# Mounting_Holes.net
KiCad netlist of a schematic drawn in Altium Designer
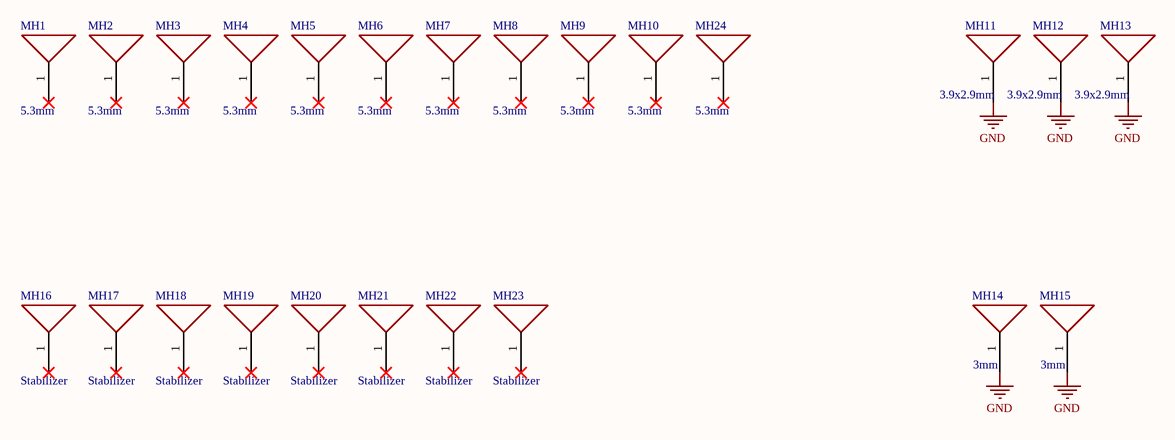
[diagram p0: Mounting_Holes.SchDoc]

(export (version "E")
  (design (tool "Eeschema 10.0.6"))
  (components
    (comp (ref "MH1")
      (value "5.3mm")
      (footprint "MTH_ROUND_5.35D")
      (libsource (lib "KeyBored_PCB_ThomasLajoie_2025") (part "Mounting Hole"))
    )
    (comp (ref "MH2")
      (value "5.3mm")
      (footprint "MTH_ROUND_5.35D")
      (libsource (lib "KeyBored_PCB_ThomasLajoie_2025") (part "Mounting Hole"))
    )
    (comp (ref "MH3")
      (value "5.3mm")
      (footprint "MTH_ROUND_5.35D")
      (libsource (lib "KeyBored_PCB_ThomasLajoie_2025") (part "Mounting Hole"))
    )
    (comp (ref "MH4")
      (value "5.3mm")
      (footprint "MTH_ROUND_5.35D")
      (libsource (lib "KeyBored_PCB_ThomasLajoie_2025") (part "Mounting Hole"))
    )
    (comp (ref "MH5")
      (value "5.3mm")
      (footprint "MTH_ROUND_5.35D")
      (libsource (lib "KeyBored_PCB_ThomasLajoie_2025") (part "Mounting Hole"))
    )
    (comp (ref "MH6")
      (value "5.3mm")
      (footprint "MTH_ROUND_5.35D")
      (libsource (lib "KeyBored_PCB_ThomasLajoie_2025") (part "Mounting Hole"))
    )
    (comp (ref "MH7")
      (value "5.3mm")
      (footprint "MTH_ROUND_5.35D")
      (libsource (lib "KeyBored_PCB_ThomasLajoie_2025") (part "Mounting Hole"))
    )
    (comp (ref "MH8")
      (value "5.3mm")
      (footprint "MTH_ROUND_5.35D")
      (libsource (lib "KeyBored_PCB_ThomasLajoie_2025") (part "Mounting Hole"))
    )
    (comp (ref "MH9")
      (value "5.3mm")
      (footprint "MTH_ROUND_5.35D")
      (libsource (lib "KeyBored_PCB_ThomasLajoie_2025") (part "Mounting Hole"))
    )
    (comp (ref "MH10")
      (value "5.3mm")
      (footprint "MTH_ROUND_5.35D")
      (libsource (lib "KeyBored_PCB_ThomasLajoie_2025") (part "Mounting Hole"))
    )
    (comp (ref "MH11")
      (value "3.9x2.9mm")
      (footprint "MTH_OBLONG_3.9x2.9_PL")
      (libsource (lib "KeyBored_PCB_ThomasLajoie_2025") (part "Mounting Hole"))
    )
    (comp (ref "MH12")
      (value "3.9x2.9mm")
      (footprint "MTH_OBLONG_3.9x2.9_PL")
      (libsource (lib "KeyBored_PCB_ThomasLajoie_2025") (part "Mounting Hole"))
    )
    (comp (ref "MH13")
      (value "3.9x2.9mm")
      (footprint "MTH_OBLONG_3.9x2.9_PL")
      (libsource (lib "KeyBored_PCB_ThomasLajoie_2025") (part "Mounting Hole"))
    )
    (comp (ref "MH14")
      (value "3mm")
      (footprint "MTH_ROUND_3D_PL")
      (libsource (lib "KeyBored_PCB_ThomasLajoie_2025") (part "Mounting Hole"))
    )
    (comp (ref "MH15")
      (value "3mm")
      (footprint "MTH_ROUND_3D_PL")
      (libsource (lib "KeyBored_PCB_ThomasLajoie_2025") (part "Mounting Hole"))
    )
    (comp (ref "MH16")
      (value "Stabilizer")
      (footprint "STABILIZERS_HOLE")
      (libsource (lib "KeyBored_PCB_ThomasLajoie_2025") (part "Mounting Hole"))
    )
    (comp (ref "MH17")
      (value "Stabilizer")
      (footprint "STABILIZERS_HOLE")
      (libsource (lib "KeyBored_PCB_ThomasLajoie_2025") (part "Mounting Hole"))
    )
    (comp (ref "MH18")
      (value "Stabilizer")
      (footprint "STABILIZERS_HOLE")
      (libsource (lib "KeyBored_PCB_ThomasLajoie_2025") (part "Mounting Hole"))
    )
    (comp (ref "MH19")
      (value "Stabilizer")
      (footprint "STABILIZERS_HOLE")
      (libsource (lib "KeyBored_PCB_ThomasLajoie_2025") (part "Mounting Hole"))
    )
    (comp (ref "MH20")
      (value "Stabilizer")
      (footprint "STABILIZERS_HOLE")
      (libsource (lib "KeyBored_PCB_ThomasLajoie_2025") (part "Mounting Hole"))
    )
    (comp (ref "MH21")
      (value "Stabilizer")
      (footprint "STABILIZERS_HOLE")
      (libsource (lib "KeyBored_PCB_ThomasLajoie_2025") (part "Mounting Hole"))
    )
    (comp (ref "MH22")
      (value "Stabilizer")
      (footprint "STABILIZERS_HOLE")
      (libsource (lib "KeyBored_PCB_ThomasLajoie_2025") (part "Mounting Hole"))
    )
    (comp (ref "MH23")
      (value "Stabilizer")
      (footprint "STABILIZERS_HOLE")
      (libsource (lib "KeyBored_PCB_ThomasLajoie_2025") (part "Mounting Hole"))
    )
    (comp (ref "MH24")
      (value "5.3mm")
      (footprint "MTH_ROUND_5.35D")
      (libsource (lib "KeyBored_PCB_ThomasLajoie_2025") (part "Mounting Hole"))
    )
  )
  (nets
    (net (code "1") (name "GND") (class "Default")
      (node (ref "MH11") (pin "1") (pintype "power_in"))
      (node (ref "MH12") (pin "1") (pintype "power_in"))
      (node (ref "MH13") (pin "1") (pintype "power_in"))
      (node (ref "MH14") (pin "1") (pintype "power_in"))
      (node (ref "MH15") (pin "1") (pintype "power_in"))
    )
    (net (code "2") (name "unconnected-(MH1-Pad1)") (class "Default")
      (node (ref "MH1") (pin "1") (pintype "power_in+no_connect"))
    )
    (net (code "3") (name "unconnected-(MH2-Pad1)") (class "Default")
      (node (ref "MH2") (pin "1") (pintype "power_in+no_connect"))
    )
    (net (code "4") (name "unconnected-(MH3-Pad1)") (class "Default")
      (node (ref "MH3") (pin "1") (pintype "power_in+no_connect"))
    )
    (net (code "5") (name "unconnected-(MH4-Pad1)") (class "Default")
      (node (ref "MH4") (pin "1") (pintype "power_in+no_connect"))
    )
    (net (code "6") (name "unconnected-(MH5-Pad1)") (class "Default")
      (node (ref "MH5") (pin "1") (pintype "power_in+no_connect"))
    )
    (net (code "7") (name "unconnected-(MH6-Pad1)") (class "Default")
      (node (ref "MH6") (pin "1") (pintype "power_in+no_connect"))
    )
    (net (code "8") (name "unconnected-(MH7-Pad1)") (class "Default")
      (node (ref "MH7") (pin "1") (pintype "power_in+no_connect"))
    )
    (net (code "9") (name "unconnected-(MH8-Pad1)") (class "Default")
      (node (ref "MH8") (pin "1") (pintype "power_in+no_connect"))
    )
    (net (code "10") (name "unconnected-(MH9-Pad1)") (class "Default")
      (node (ref "MH9") (pin "1") (pintype "power_in+no_connect"))
    )
    (net (code "11") (name "unconnected-(MH10-Pad1)") (class "Default")
      (node (ref "MH10") (pin "1") (pintype "power_in+no_connect"))
    )
    (net (code "12") (name "unconnected-(MH16-Pad1)") (class "Default")
      (node (ref "MH16") (pin "1") (pintype "power_in+no_connect"))
    )
    (net (code "13") (name "unconnected-(MH17-Pad1)") (class "Default")
      (node (ref "MH17") (pin "1") (pintype "power_in+no_connect"))
    )
    (net (code "14") (name "unconnected-(MH18-Pad1)") (class "Default")
      (node (ref "MH18") (pin "1") (pintype "power_in+no_connect"))
    )
    (net (code "15") (name "unconnected-(MH19-Pad1)") (class "Default")
      (node (ref "MH19") (pin "1") (pintype "power_in+no_connect"))
    )
    (net (code "16") (name "unconnected-(MH20-Pad1)") (class "Default")
      (node (ref "MH20") (pin "1") (pintype "power_in+no_connect"))
    )
    (net (code "17") (name "unconnected-(MH21-Pad1)") (class "Default")
      (node (ref "MH21") (pin "1") (pintype "power_in+no_connect"))
    )
    (net (code "18") (name "unconnected-(MH22-Pad1)") (class "Default")
      (node (ref "MH22") (pin "1") (pintype "power_in+no_connect"))
    )
    (net (code "19") (name "unconnected-(MH23-Pad1)") (class "Default")
      (node (ref "MH23") (pin "1") (pintype "power_in+no_connect"))
    )
    (net (code "20") (name "unconnected-(MH24-Pad1)") (class "Default")
      (node (ref "MH24") (pin "1") (pintype "power_in+no_connect"))
    )
  )
)
